# Ulimate.net
KiCad netlist of a schematic drawn in EAGLE
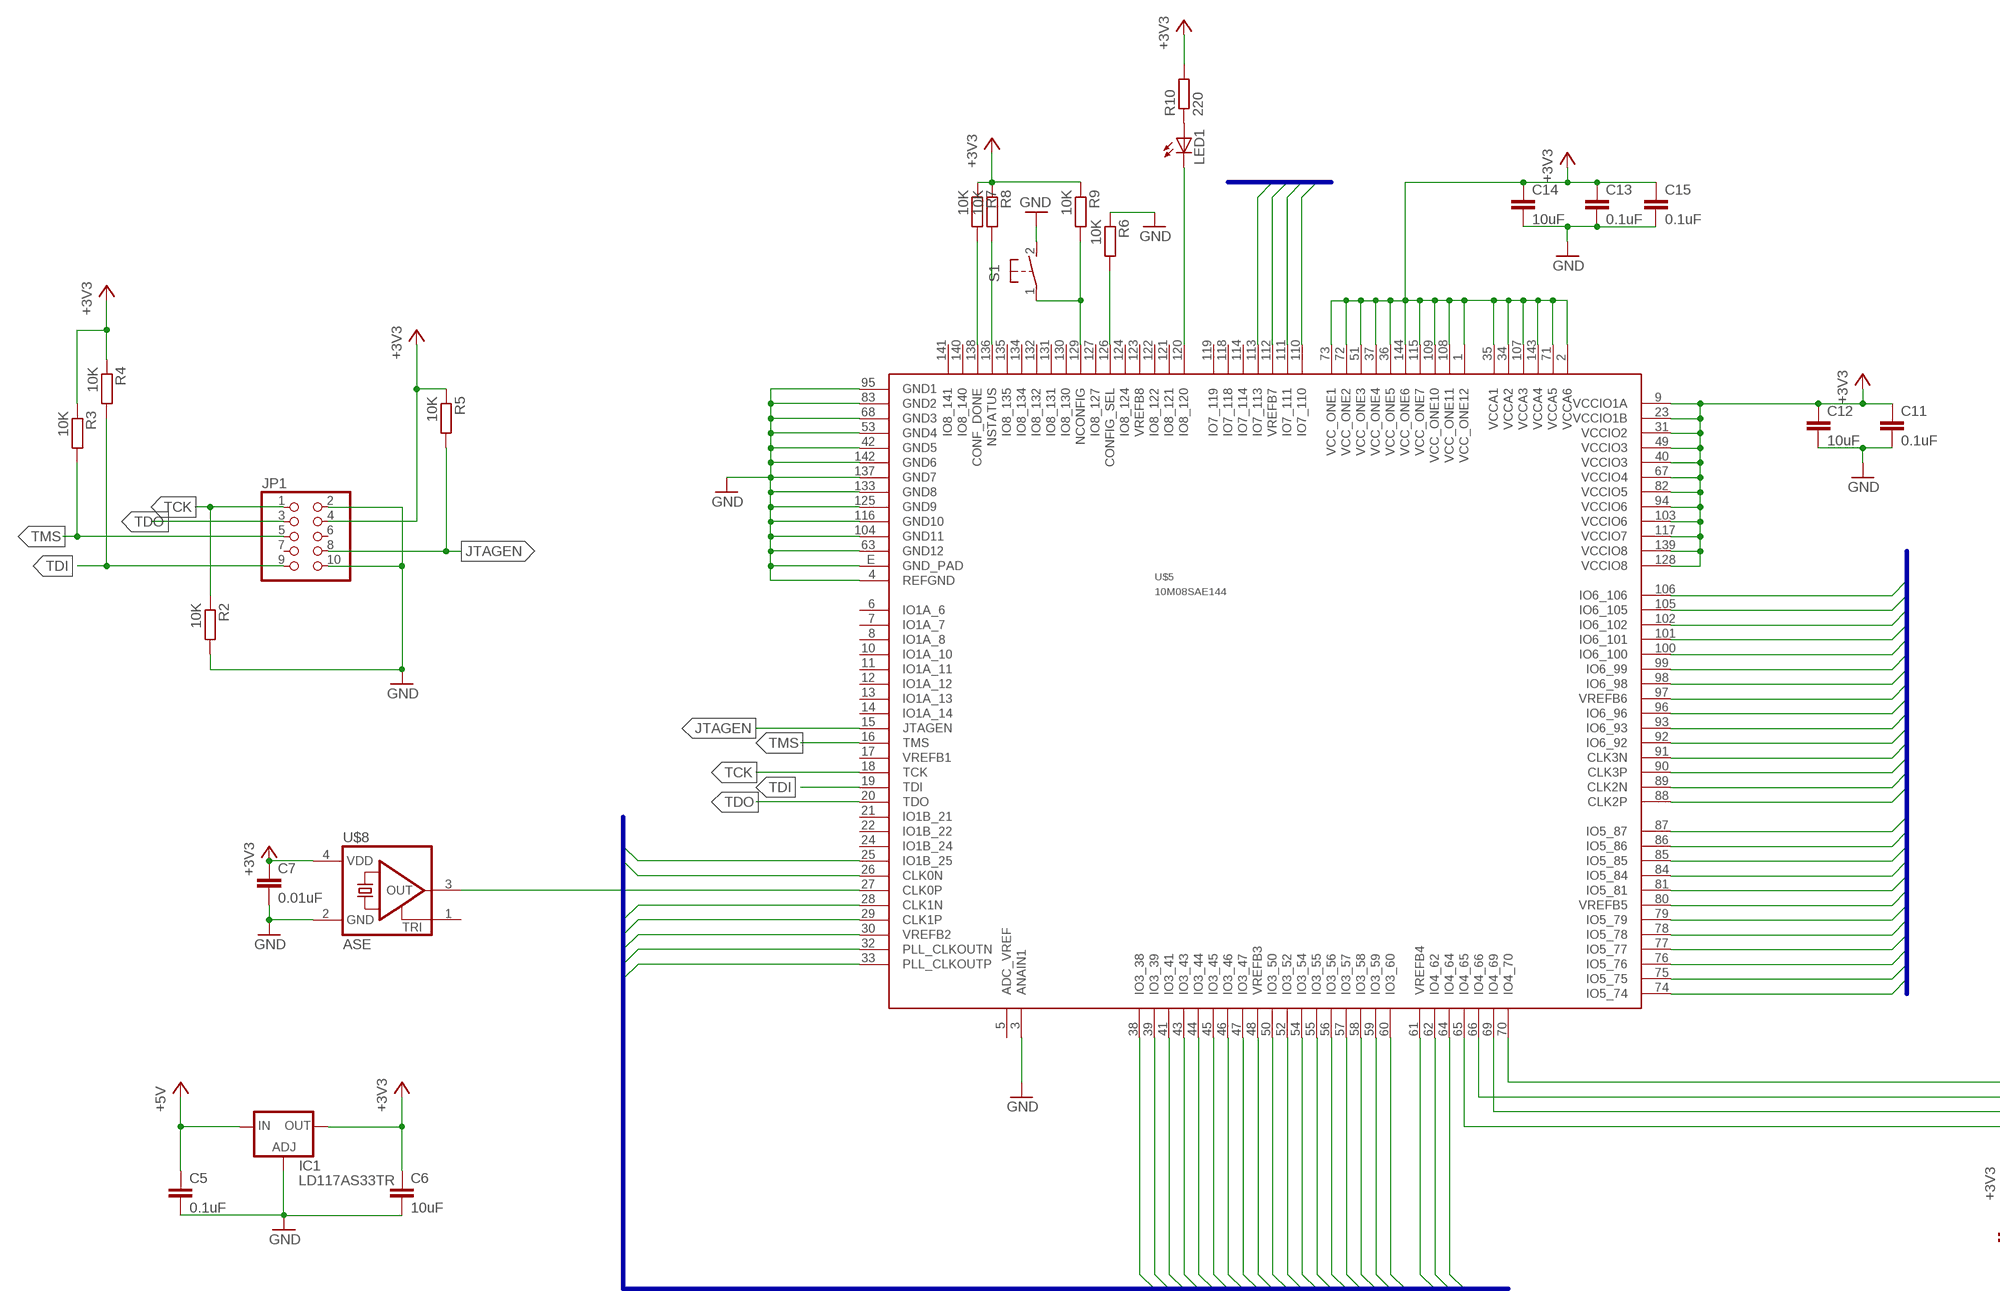
[diagram p0: schematic, sheet 1, part 1 of 2]
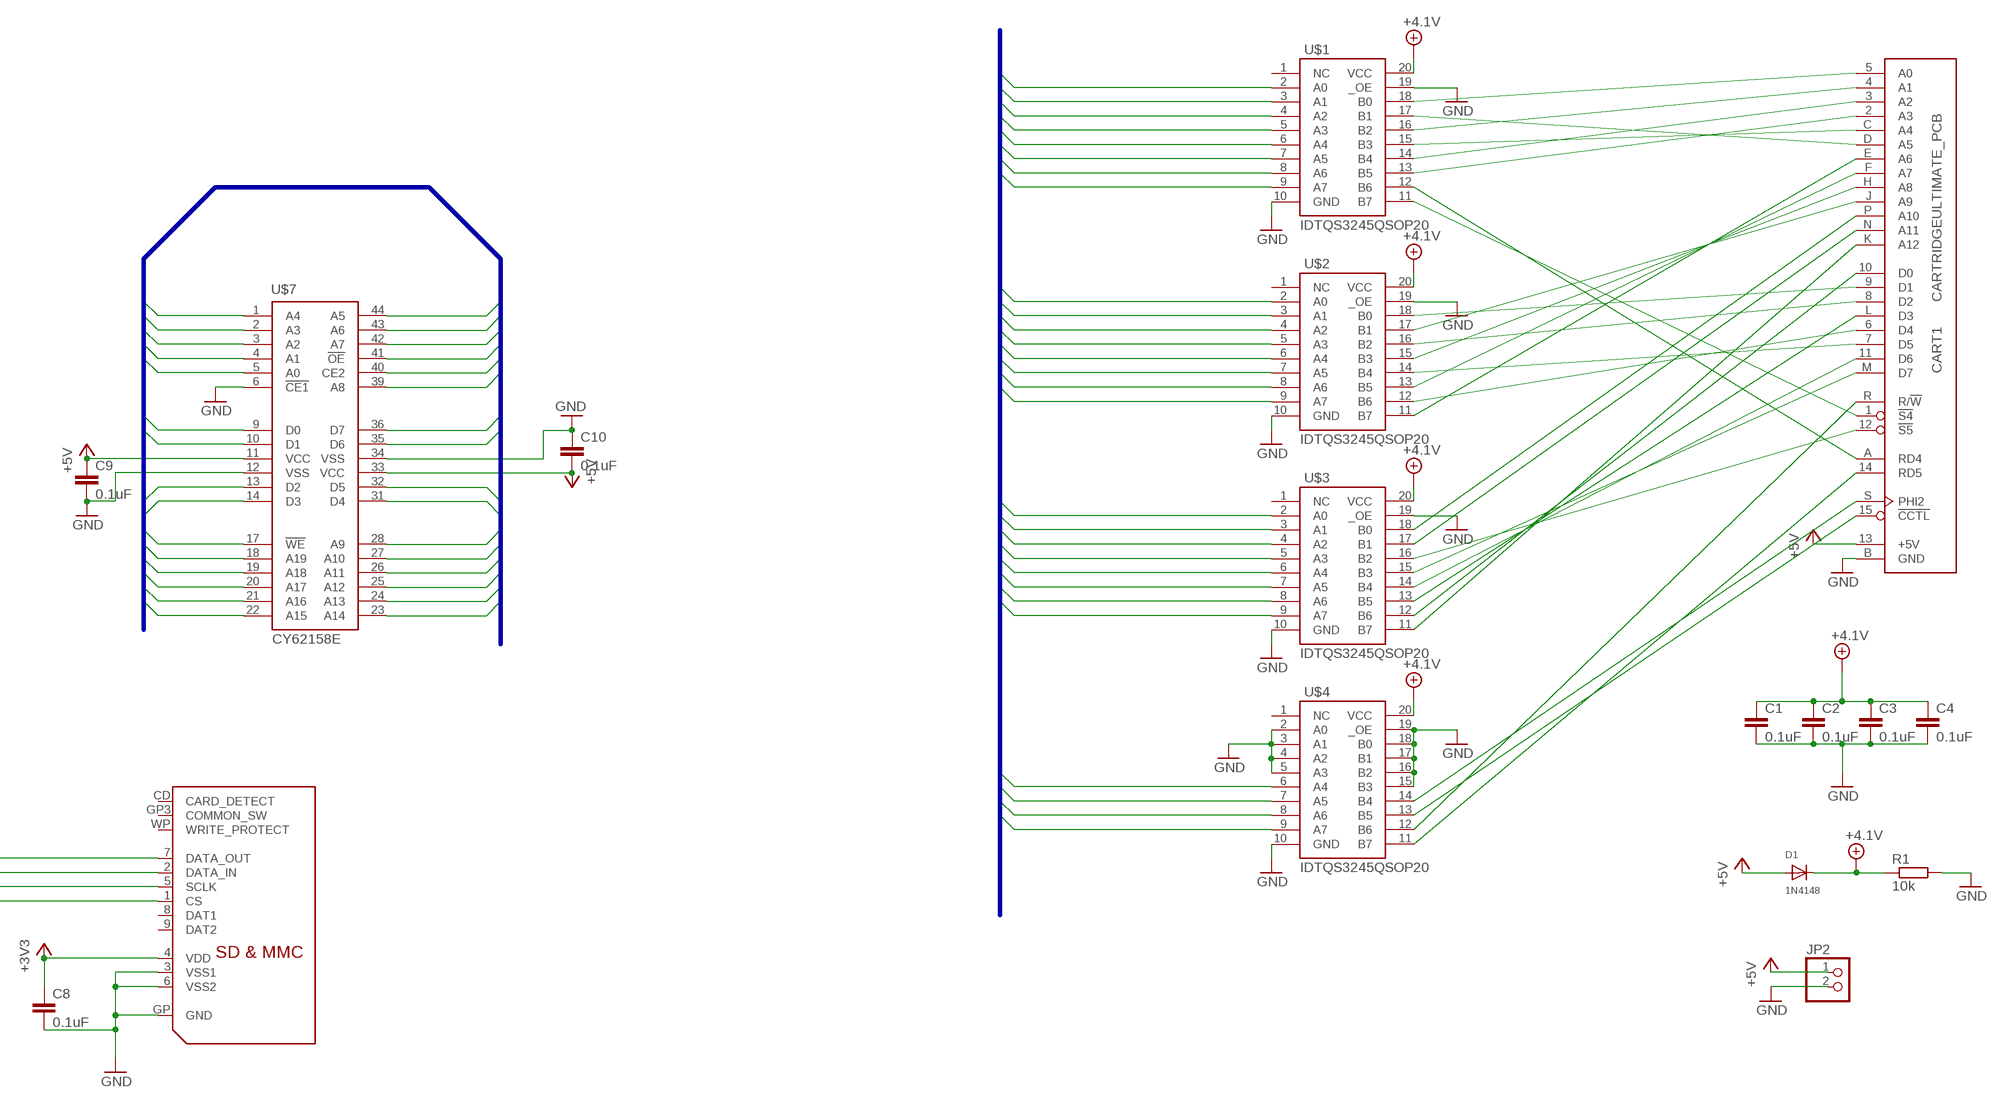
[diagram p1: schematic, sheet 1, part 2 of 2]

(export (version "E")
  (design (tool "Eeschema 10.0.6"))
  (components
    (comp (ref "C1")
      (value "0.1uF")
      (footprint "eagle-import:C0805K")
      (libsource (lib "eagle-import") (part "C-EUC0805K"))
    )
    (comp (ref "C2")
      (value "0.1uF")
      (footprint "eagle-import:C0805K")
      (libsource (lib "eagle-import") (part "C-EUC0805K"))
    )
    (comp (ref "C3")
      (value "0.1uF")
      (footprint "eagle-import:C0805K")
      (libsource (lib "eagle-import") (part "C-EUC0805K"))
    )
    (comp (ref "C4")
      (value "0.1uF")
      (footprint "eagle-import:C0805K")
      (libsource (lib "eagle-import") (part "C-EUC0805K"))
    )
    (comp (ref "C5")
      (value "0.1uF")
      (footprint "eagle-import:C0805K")
      (libsource (lib "eagle-import") (part "C-EUC0805K"))
    )
    (comp (ref "C6")
      (value "10uF")
      (footprint "eagle-import:C0805K")
      (libsource (lib "eagle-import") (part "C-EUC0805K"))
    )
    (comp (ref "C7")
      (value "0.01uF")
      (footprint "eagle-import:C0805K")
      (libsource (lib "eagle-import") (part "C-EUC0805K"))
    )
    (comp (ref "C8")
      (value "0.1uF")
      (footprint "eagle-import:C0805K")
      (libsource (lib "eagle-import") (part "C-EUC0805K"))
    )
    (comp (ref "C9")
      (value "0.1uF")
      (footprint "eagle-import:C0805K")
      (libsource (lib "eagle-import") (part "C-EUC0805K"))
    )
    (comp (ref "C10")
      (value "0.1uF")
      (footprint "eagle-import:C0805K")
      (libsource (lib "eagle-import") (part "C-EUC0805K"))
    )
    (comp (ref "C11")
      (value "0.1uF")
      (footprint "eagle-import:C0805K")
      (libsource (lib "eagle-import") (part "C-EUC0805K"))
    )
    (comp (ref "C12")
      (value "10uF")
      (footprint "eagle-import:C0805K")
      (libsource (lib "eagle-import") (part "C-EUC0805K"))
    )
    (comp (ref "C13")
      (value "0.1uF")
      (footprint "eagle-import:C0805K")
      (libsource (lib "eagle-import") (part "C-EUC0805K"))
    )
    (comp (ref "C14")
      (value "10uF")
      (footprint "eagle-import:C0805K")
      (libsource (lib "eagle-import") (part "C-EUC0805K"))
    )
    (comp (ref "C15")
      (value "0.1uF")
      (footprint "eagle-import:C0805K")
      (libsource (lib "eagle-import") (part "C-EUC0805K"))
    )
    (comp (ref "CART1")
      (value "CARTRIDGEULTIMATE_PCB")
      (footprint "eagle-import:CART_ULTIMATE")
      (libsource (lib "eagle-import") (part "CARTRIDGEULTIMATE_PCB"))
    )
    (comp (ref "D1")
      (value "1N4148")
      (footprint "eagle-import:SOD-123FL")
      (libsource (lib "eagle-import") (part "DIODE_SOD-123FL"))
    )
    (comp (ref "IC1")
      (value "LD117AS33TR")
      (footprint "eagle-import:SOT223")
      (libsource (lib "eagle-import") (part "LD117A?S33TR"))
    )
    (comp (ref "JP1")
      (value "PINHD-2X5")
      (footprint "eagle-import:2X05")
      (libsource (lib "eagle-import") (part "PINHD-2X5"))
    )
    (comp (ref "JP2")
      (value "PINHD-1X2")
      (footprint "eagle-import:1X02")
      (libsource (lib "eagle-import") (part "PINHD-1X2"))
    )
    (comp (ref "LED1")
      (value "LEDSML0805")
      (footprint "eagle-import:SML0805")
      (libsource (lib "eagle-import") (part "LEDSML0805"))
    )
    (comp (ref "R1")
      (value "10k")
      (footprint "eagle-import:R0805")
      (libsource (lib "eagle-import") (part "R-EU_R0805"))
    )
    (comp (ref "R2")
      (value "10K")
      (footprint "eagle-import:R0805")
      (libsource (lib "eagle-import") (part "R-EU_R0805"))
    )
    (comp (ref "R3")
      (value "10K")
      (footprint "eagle-import:R0805")
      (libsource (lib "eagle-import") (part "R-EU_R0805"))
    )
    (comp (ref "R4")
      (value "10K")
      (footprint "eagle-import:R0805")
      (libsource (lib "eagle-import") (part "R-EU_R0805"))
    )
    (comp (ref "R5")
      (value "10K")
      (footprint "eagle-import:R0805")
      (libsource (lib "eagle-import") (part "R-EU_R0805"))
    )
    (comp (ref "R6")
      (value "10K")
      (footprint "eagle-import:R0805")
      (libsource (lib "eagle-import") (part "R-EU_R0805"))
    )
    (comp (ref "R7")
      (value "10K")
      (footprint "eagle-import:R0805")
      (libsource (lib "eagle-import") (part "R-EU_R0805"))
    )
    (comp (ref "R8")
      (value "10K")
      (footprint "eagle-import:R0805")
      (libsource (lib "eagle-import") (part "R-EU_R0805"))
    )
    (comp (ref "R9")
      (value "10K")
      (footprint "eagle-import:R0805")
      (libsource (lib "eagle-import") (part "R-EU_R0805"))
    )
    (comp (ref "R10")
      (value "220")
      (footprint "eagle-import:R0805")
      (libsource (lib "eagle-import") (part "R-EU_R0805"))
    )
    (comp (ref "S1")
      (value "31-XXSKINNY")
      (footprint "eagle-import:B3F-31XX-SKINNIER")
      (libsource (lib "eagle-import") (part "31-XXSKINNY"))
    )
    (comp (ref "U$1")
      (value "IDTQS3245QSOP20")
      (footprint "eagle-import:QSOP20")
      (libsource (lib "eagle-import") (part "IDTQS3245QSOP20"))
    )
    (comp (ref "U$2")
      (value "IDTQS3245QSOP20")
      (footprint "eagle-import:QSOP20")
      (libsource (lib "eagle-import") (part "IDTQS3245QSOP20"))
    )
    (comp (ref "U$3")
      (value "IDTQS3245QSOP20")
      (footprint "eagle-import:QSOP20")
      (libsource (lib "eagle-import") (part "IDTQS3245QSOP20"))
    )
    (comp (ref "U$4")
      (value "IDTQS3245QSOP20")
      (footprint "eagle-import:QSOP20")
      (libsource (lib "eagle-import") (part "IDTQS3245QSOP20"))
    )
    (comp (ref "U$5")
      (value "10M08SAE144")
      (footprint "eagle-import:EQFP144")
      (libsource (lib "eagle-import") (part "10M08SAE144"))
    )
    (comp (ref "U$6")
      (value "SDMMC06132")
      (footprint "eagle-import:06132")
      (libsource (lib "eagle-import") (part "SDMMC06132"))
    )
    (comp (ref "U$7")
      (value "CY62158E")
      (footprint "eagle-import:TSOP44-II")
      (libsource (lib "eagle-import") (part "CY62158E"))
    )
    (comp (ref "U$8")
      (value "ASE")
      (footprint "eagle-import:ASE")
      (libsource (lib "eagle-import") (part "ASE"))
    )
  )
  (nets
    (net (code "1") (name "+3V3") (class "Default")
      (node (ref "C11") (pin "1") (pinfunction "1_1") (pintype "passive"))
      (node (ref "C12") (pin "1") (pinfunction "1_1") (pintype "passive"))
      (node (ref "C13") (pin "1") (pinfunction "1_1") (pintype "passive"))
      (node (ref "C14") (pin "1") (pinfunction "1_1") (pintype "passive"))
      (node (ref "C15") (pin "1") (pinfunction "1_1") (pintype "passive"))
      (node (ref "C6") (pin "1") (pinfunction "1_1") (pintype "passive"))
      (node (ref "C7") (pin "1") (pinfunction "1_1") (pintype "passive"))
      (node (ref "C8") (pin "1") (pinfunction "1_1") (pintype "passive"))
      (node (ref "IC1") (pin "4") (pinfunction "OUT_4") (pintype "passive"))
      (node (ref "JP1") (pin "4") (pinfunction "4_4") (pintype "passive"))
      (node (ref "R10") (pin "2") (pinfunction "2_2") (pintype "passive"))
      (node (ref "R3") (pin "1") (pinfunction "1_1") (pintype "passive"))
      (node (ref "R4") (pin "1") (pinfunction "1_1") (pintype "passive"))
      (node (ref "R5") (pin "1") (pinfunction "1_1") (pintype "passive"))
      (node (ref "R7") (pin "1") (pinfunction "1_1") (pintype "passive"))
      (node (ref "R8") (pin "1") (pinfunction "1_1") (pintype "passive"))
      (node (ref "R9") (pin "1") (pinfunction "1_1") (pintype "passive"))
      (node (ref "U$5") (pin "1") (pinfunction "VCC_ONE12_1") (pintype "bidirectional"))
      (node (ref "U$5") (pin "103") (pinfunction "VCCIO6_103") (pintype "bidirectional"))
      (node (ref "U$5") (pin "107") (pinfunction "VCCA3_107") (pintype "bidirectional"))
      (node (ref "U$5") (pin "108") (pinfunction "VCC_ONE11_108") (pintype "bidirectional"))
      (node (ref "U$5") (pin "109") (pinfunction "VCC_ONE10_109") (pintype "bidirectional"))
      (node (ref "U$5") (pin "115") (pinfunction "VCC_ONE7_115") (pintype "bidirectional"))
      (node (ref "U$5") (pin "117") (pinfunction "VCCIO7_117") (pintype "bidirectional"))
      (node (ref "U$5") (pin "128") (pinfunction "VCCIO8_128") (pintype "bidirectional"))
      (node (ref "U$5") (pin "139") (pinfunction "VCCIO8_139") (pintype "bidirectional"))
      (node (ref "U$5") (pin "143") (pinfunction "VCCA4_143") (pintype "bidirectional"))
      (node (ref "U$5") (pin "144") (pinfunction "VCC_ONE6_144") (pintype "bidirectional"))
      (node (ref "U$5") (pin "2") (pinfunction "VCCA6_2") (pintype "bidirectional"))
      (node (ref "U$5") (pin "23") (pinfunction "VCCIO1B_23") (pintype "bidirectional"))
      (node (ref "U$5") (pin "31") (pinfunction "VCCIO2_31") (pintype "bidirectional"))
      (node (ref "U$5") (pin "34") (pinfunction "VCCA2_34") (pintype "bidirectional"))
      (node (ref "U$5") (pin "35") (pinfunction "VCCA1_35") (pintype "bidirectional"))
      (node (ref "U$5") (pin "36") (pinfunction "VCC_ONE5_36") (pintype "bidirectional"))
      (node (ref "U$5") (pin "37") (pinfunction "VCC_ONE4_37") (pintype "bidirectional"))
      (node (ref "U$5") (pin "40") (pinfunction "VCCIO3_40") (pintype "bidirectional"))
      (node (ref "U$5") (pin "49") (pinfunction "VCCIO3_49") (pintype "bidirectional"))
      (node (ref "U$5") (pin "51") (pinfunction "VCC_ONE3_51") (pintype "bidirectional"))
      (node (ref "U$5") (pin "67") (pinfunction "VCCIO4_67") (pintype "bidirectional"))
      (node (ref "U$5") (pin "71") (pinfunction "VCCA5_71") (pintype "bidirectional"))
      (node (ref "U$5") (pin "72") (pinfunction "VCC_ONE2_72") (pintype "bidirectional"))
      (node (ref "U$5") (pin "73") (pinfunction "VCC_ONE1_73") (pintype "bidirectional"))
      (node (ref "U$5") (pin "82") (pinfunction "VCCIO5_82") (pintype "bidirectional"))
      (node (ref "U$5") (pin "9") (pinfunction "VCCIO1A_9") (pintype "bidirectional"))
      (node (ref "U$5") (pin "94") (pinfunction "VCCIO6_94") (pintype "bidirectional"))
      (node (ref "U$6") (pin "4") (pinfunction "VDD_4") (pintype "power_in"))
      (node (ref "U$8") (pin "4") (pinfunction "VDD_4") (pintype "power_in"))
    )
    (net (code "2") (name "+4.1V") (class "Default")
      (node (ref "C1") (pin "1") (pinfunction "1_1") (pintype "passive"))
      (node (ref "C2") (pin "1") (pinfunction "1_1") (pintype "passive"))
      (node (ref "C3") (pin "1") (pinfunction "1_1") (pintype "passive"))
      (node (ref "C4") (pin "1") (pinfunction "1_1") (pintype "passive"))
      (node (ref "D1") (pin "C") (pinfunction "C_C") (pintype "passive"))
      (node (ref "R1") (pin "1") (pinfunction "1_1") (pintype "passive"))
      (node (ref "U$1") (pin "20") (pinfunction "VCC_20") (pintype "power_in"))
      (node (ref "U$2") (pin "20") (pinfunction "VCC_20") (pintype "power_in"))
      (node (ref "U$3") (pin "20") (pinfunction "VCC_20") (pintype "power_in"))
      (node (ref "U$4") (pin "20") (pinfunction "VCC_20") (pintype "power_in"))
    )
    (net (code "3") (name "+5V") (class "Default")
      (node (ref "C10") (pin "2") (pinfunction "2_2") (pintype "passive"))
      (node (ref "C5") (pin "1") (pinfunction "1_1") (pintype "passive"))
      (node (ref "C9") (pin "1") (pinfunction "1_1") (pintype "passive"))
      (node (ref "CART1") (pin "13") (pinfunction "+5V_13") (pintype "power_in"))
      (node (ref "D1") (pin "A") (pinfunction "A_A") (pintype "passive"))
      (node (ref "IC1") (pin "3") (pinfunction "IN_3") (pintype "input"))
      (node (ref "JP2") (pin "1") (pinfunction "1_1") (pintype "passive"))
      (node (ref "U$7") (pin "11") (pinfunction "VCC_11") (pintype "bidirectional"))
      (node (ref "U$7") (pin "33") (pinfunction "VCC_33") (pintype "bidirectional"))
    )
    (net (code "4") (name "/A0") (class "Default")
      (node (ref "U$5") (pin "96") (pinfunction "IO6_96_96") (pintype "bidirectional"))
      (node (ref "U$7") (pin "5") (pinfunction "A0_5") (pintype "bidirectional"))
    )
    (net (code "5") (name "/A1") (class "Default")
      (node (ref "U$5") (pin "97") (pinfunction "VREFB6_97") (pintype "bidirectional"))
      (node (ref "U$7") (pin "4") (pinfunction "A1_4") (pintype "bidirectional"))
    )
    (net (code "6") (name "/A2") (class "Default")
      (node (ref "U$5") (pin "98") (pinfunction "IO6_98_98") (pintype "bidirectional"))
      (node (ref "U$7") (pin "3") (pinfunction "A2_3") (pintype "bidirectional"))
    )
    (net (code "7") (name "/A3") (class "Default")
      (node (ref "U$5") (pin "99") (pinfunction "IO6_99_99") (pintype "bidirectional"))
      (node (ref "U$7") (pin "2") (pinfunction "A3_2") (pintype "bidirectional"))
    )
    (net (code "8") (name "/A4") (class "Default")
      (node (ref "U$5") (pin "100") (pinfunction "IO6_100_100") (pintype "bidirectional"))
      (node (ref "U$7") (pin "1") (pinfunction "A4_1") (pintype "bidirectional"))
    )
    (net (code "9") (name "/A5") (class "Default")
      (node (ref "U$5") (pin "105") (pinfunction "IO6_105_105") (pintype "bidirectional"))
      (node (ref "U$7") (pin "44") (pinfunction "A5_44") (pintype "bidirectional"))
    )
    (net (code "10") (name "/A6") (class "Default")
      (node (ref "U$5") (pin "102") (pinfunction "IO6_102_102") (pintype "bidirectional"))
      (node (ref "U$7") (pin "43") (pinfunction "A6_43") (pintype "bidirectional"))
    )
    (net (code "11") (name "/A7") (class "Default")
      (node (ref "U$5") (pin "101") (pinfunction "IO6_101_101") (pintype "bidirectional"))
      (node (ref "U$7") (pin "42") (pinfunction "A7_42") (pintype "bidirectional"))
    )
    (net (code "12") (name "/A8") (class "Default")
      (node (ref "U$5") (pin "111") (pinfunction "IO7_111_111") (pintype "bidirectional"))
      (node (ref "U$7") (pin "39") (pinfunction "A8_39") (pintype "bidirectional"))
    )
    (net (code "13") (name "/A9") (class "Default")
      (node (ref "U$5") (pin "76") (pinfunction "IO5_76_76") (pintype "bidirectional"))
      (node (ref "U$7") (pin "28") (pinfunction "A9_28") (pintype "bidirectional"))
    )
    (net (code "14") (name "/A10") (class "Default")
      (node (ref "U$5") (pin "77") (pinfunction "IO5_77_77") (pintype "bidirectional"))
      (node (ref "U$7") (pin "27") (pinfunction "A10_27") (pintype "bidirectional"))
    )
    (net (code "15") (name "/A11") (class "Default")
      (node (ref "U$5") (pin "78") (pinfunction "IO5_78_78") (pintype "bidirectional"))
      (node (ref "U$7") (pin "26") (pinfunction "A11_26") (pintype "bidirectional"))
    )
    (net (code "16") (name "/A12") (class "Default")
      (node (ref "U$5") (pin "79") (pinfunction "IO5_79_79") (pintype "bidirectional"))
      (node (ref "U$7") (pin "25") (pinfunction "A12_25") (pintype "bidirectional"))
    )
    (net (code "17") (name "/A13") (class "Default")
      (node (ref "U$5") (pin "80") (pinfunction "VREFB5_80") (pintype "bidirectional"))
      (node (ref "U$7") (pin "24") (pinfunction "A13_24") (pintype "bidirectional"))
    )
    (net (code "18") (name "/A14") (class "Default")
      (node (ref "U$5") (pin "81") (pinfunction "IO5_81_81") (pintype "bidirectional"))
      (node (ref "U$7") (pin "23") (pinfunction "A14_23") (pintype "bidirectional"))
    )
    (net (code "19") (name "/A15") (class "Default")
      (node (ref "U$5") (pin "84") (pinfunction "IO5_84_84") (pintype "bidirectional"))
      (node (ref "U$7") (pin "22") (pinfunction "A15_22") (pintype "bidirectional"))
    )
    (net (code "20") (name "/A16") (class "Default")
      (node (ref "U$5") (pin "85") (pinfunction "IO5_85_85") (pintype "bidirectional"))
      (node (ref "U$7") (pin "21") (pinfunction "A16_21") (pintype "bidirectional"))
    )
    (net (code "21") (name "/A17") (class "Default")
      (node (ref "U$5") (pin "86") (pinfunction "IO5_86_86") (pintype "bidirectional"))
      (node (ref "U$7") (pin "20") (pinfunction "A17_20") (pintype "bidirectional"))
    )
    (net (code "22") (name "/A18") (class "Default")
      (node (ref "U$5") (pin "87") (pinfunction "IO5_87_87") (pintype "bidirectional"))
      (node (ref "U$7") (pin "19") (pinfunction "A18_19") (pintype "bidirectional"))
    )
    (net (code "23") (name "/A19") (class "Default")
      (node (ref "U$5") (pin "88") (pinfunction "CLK2P_88") (pintype "bidirectional"))
      (node (ref "U$7") (pin "18") (pinfunction "A19_18") (pintype "bidirectional"))
    )
    (net (code "24") (name "/CART_A0") (class "Default")
      (node (ref "U$1") (pin "2") (pinfunction "A0_2") (pintype "bidirectional"))
      (node (ref "U$5") (pin "39") (pinfunction "IO3_39_39") (pintype "bidirectional"))
    )
    (net (code "25") (name "/CART_A1") (class "Default")
      (node (ref "U$1") (pin "4") (pinfunction "A2_4") (pintype "bidirectional"))
      (node (ref "U$5") (pin "33") (pinfunction "PLL_CLKOUTP_33") (pintype "bidirectional"))
    )
    (net (code "26") (name "/CART_A2") (class "Default")
      (node (ref "U$1") (pin "6") (pinfunction "A4_6") (pintype "bidirectional"))
      (node (ref "U$5") (pin "30") (pinfunction "VREFB2_30") (pintype "bidirectional"))
    )
    (net (code "27") (name "/CART_A3") (class "Default")
      (node (ref "U$1") (pin "7") (pinfunction "A5_7") (pintype "bidirectional"))
      (node (ref "U$5") (pin "29") (pinfunction "CLK1P_29") (pintype "bidirectional"))
    )
    (net (code "28") (name "/CART_A4") (class "Default")
      (node (ref "U$1") (pin "5") (pinfunction "A3_5") (pintype "bidirectional"))
      (node (ref "U$5") (pin "32") (pinfunction "PLL_CLKOUTN_32") (pintype "bidirectional"))
    )
    (net (code "29") (name "/CART_A5") (class "Default")
      (node (ref "U$1") (pin "3") (pinfunction "A1_3") (pintype "bidirectional"))
      (node (ref "U$5") (pin "38") (pinfunction "IO3_38_38") (pintype "bidirectional"))
    )
    (net (code "30") (name "/CART_A6") (class "Default")
      (node (ref "U$2") (pin "9") (pinfunction "A7_9") (pintype "bidirectional"))
      (node (ref "U$5") (pin "41") (pinfunction "IO3_41_41") (pintype "bidirectional"))
    )
    (net (code "31") (name "/CART_A7") (class "Default")
      (node (ref "U$2") (pin "7") (pinfunction "A5_7") (pintype "bidirectional"))
      (node (ref "U$5") (pin "44") (pinfunction "IO3_44_44") (pintype "bidirectional"))
    )
    (net (code "32") (name "/CART_A8") (class "Default")
      (node (ref "U$2") (pin "5") (pinfunction "A3_5") (pintype "bidirectional"))
      (node (ref "U$5") (pin "46") (pinfunction "IO3_46_46") (pintype "bidirectional"))
    )
    (net (code "33") (name "/CART_A9") (class "Default")
      (node (ref "U$2") (pin "3") (pinfunction "A1_3") (pintype "bidirectional"))
      (node (ref "U$5") (pin "48") (pinfunction "VREFB3_48") (pintype "bidirectional"))
    )
    (net (code "34") (name "/CART_A10") (class "Default")
      (node (ref "U$3") (pin "2") (pinfunction "A0_2") (pintype "bidirectional"))
      (node (ref "U$5") (pin "60") (pinfunction "IO3_60_60") (pintype "bidirectional"))
    )
    (net (code "35") (name "/CART_A11") (class "Default")
      (node (ref "U$3") (pin "3") (pinfunction "A1_3") (pintype "bidirectional"))
      (node (ref "U$5") (pin "59") (pinfunction "IO3_59_59") (pintype "bidirectional"))
    )
    (net (code "36") (name "/CART_A12") (class "Default")
      (node (ref "U$3") (pin "9") (pinfunction "A7_9") (pintype "bidirectional"))
      (node (ref "U$5") (pin "52") (pinfunction "IO3_52_52") (pintype "bidirectional"))
    )
    (net (code "37") (name "/CART_CTL") (class "Default")
      (node (ref "U$4") (pin "7") (pinfunction "A5_7") (pintype "bidirectional"))
      (node (ref "U$5") (pin "64") (pinfunction "IO4_64_64") (pintype "bidirectional"))
    )
    (net (code "38") (name "/CART_D0") (class "Default")
      (node (ref "U$3") (pin "8") (pinfunction "A6_8") (pintype "bidirectional"))
      (node (ref "U$5") (pin "54") (pinfunction "IO3_54_54") (pintype "bidirectional"))
    )
    (net (code "39") (name "/CART_D1") (class "Default")
      (node (ref "U$2") (pin "2") (pinfunction "A0_2") (pintype "bidirectional"))
      (node (ref "U$5") (pin "50") (pinfunction "IO3_50_50") (pintype "bidirectional"))
    )
    (net (code "40") (name "/CART_D2") (class "Default")
      (node (ref "U$2") (pin "4") (pinfunction "A2_4") (pintype "bidirectional"))
      (node (ref "U$5") (pin "47") (pinfunction "IO3_47_47") (pintype "bidirectional"))
    )
    (net (code "41") (name "/CART_D3") (class "Default")
      (node (ref "U$3") (pin "7") (pinfunction "A5_7") (pintype "bidirectional"))
      (node (ref "U$5") (pin "55") (pinfunction "IO3_55_55") (pintype "bidirectional"))
    )
    (net (code "42") (name "/CART_D4") (class "Default")
      (node (ref "U$2") (pin "8") (pinfunction "A6_8") (pintype "bidirectional"))
      (node (ref "U$5") (pin "43") (pinfunction "IO3_43_43") (pintype "bidirectional"))
    )
    (net (code "43") (name "/CART_D5") (class "Default")
      (node (ref "U$2") (pin "6") (pinfunction "A4_6") (pintype "bidirectional"))
      (node (ref "U$5") (pin "45") (pinfunction "IO3_45_45") (pintype "bidirectional"))
    )
    (net (code "44") (name "/CART_D6") (class "Default")
      (node (ref "U$3") (pin "6") (pinfunction "A4_6") (pintype "bidirectional"))
      (node (ref "U$5") (pin "56") (pinfunction "IO3_56_56") (pintype "bidirectional"))
    )
    (net (code "45") (name "/CART_D7") (class "Default")
      (node (ref "U$3") (pin "5") (pinfunction "A3_5") (pintype "bidirectional"))
      (node (ref "U$5") (pin "57") (pinfunction "IO3_57_57") (pintype "bidirectional"))
    )
    (net (code "46") (name "/CART_PHI") (class "Default")
      (node (ref "U$4") (pin "6") (pinfunction "A4_6") (pintype "bidirectional"))
      (node (ref "U$5") (pin "26") (pinfunction "CLK0N_26") (pintype "bidirectional"))
    )
    (net (code "47") (name "/CART_RD4") (class "Default")
      (node (ref "U$1") (pin "8") (pinfunction "A6_8") (pintype "bidirectional"))
      (node (ref "U$5") (pin "25") (pinfunction "IO1B_25_25") (pintype "bidirectional"))
    )
    (net (code "48") (name "/CART_RD5") (class "Default")
      (node (ref "U$4") (pin "9") (pinfunction "A7_9") (pintype "bidirectional"))
      (node (ref "U$5") (pin "61") (pinfunction "VREFB4_61") (pintype "bidirectional"))
    )
    (net (code "49") (name "/CART_RW") (class "Default")
      (node (ref "U$4") (pin "8") (pinfunction "A6_8") (pintype "bidirectional"))
      (node (ref "U$5") (pin "62") (pinfunction "IO4_62_62") (pintype "bidirectional"))
    )
    (net (code "50") (name "/CART_S4") (class "Default")
      (node (ref "U$1") (pin "9") (pinfunction "A7_9") (pintype "bidirectional"))
      (node (ref "U$5") (pin "28") (pinfunction "CLK1N_28") (pintype "bidirectional"))
    )
    (net (code "51") (name "/CART_S5") (class "Default")
      (node (ref "U$3") (pin "4") (pinfunction "A2_4") (pintype "bidirectional"))
      (node (ref "U$5") (pin "58") (pinfunction "IO3_58_58") (pintype "bidirectional"))
    )
    (net (code "52") (name "/CE") (class "Default")
      (node (ref "U$5") (pin "110") (pinfunction "IO7_110_110") (pintype "bidirectional"))
      (node (ref "U$7") (pin "40") (pinfunction "CE2_40") (pintype "bidirectional"))
    )
    (net (code "53") (name "/D0") (class "Default")
      (node (ref "U$5") (pin "93") (pinfunction "IO6_93_93") (pintype "bidirectional"))
      (node (ref "U$7") (pin "9") (pinfunction "D0_9") (pintype "bidirectional"))
    )
    (net (code "54") (name "/D1") (class "Default")
      (node (ref "U$5") (pin "92") (pinfunction "IO6_92_92") (pintype "bidirectional"))
      (node (ref "U$7") (pin "10") (pinfunction "D1_10") (pintype "bidirectional"))
    )
    (net (code "55") (name "/D2") (class "Default")
      (node (ref "U$5") (pin "91") (pinfunction "CLK3N_91") (pintype "bidirectional"))
      (node (ref "U$7") (pin "13") (pinfunction "D2_13") (pintype "bidirectional"))
    )
    (net (code "56") (name "/D3") (class "Default")
      (node (ref "U$5") (pin "90") (pinfunction "CLK3P_90") (pintype "bidirectional"))
      (node (ref "U$7") (pin "14") (pinfunction "D3_14") (pintype "bidirectional"))
    )
    (net (code "57") (name "/D4") (class "Default")
      (node (ref "U$5") (pin "75") (pinfunction "IO5_75_75") (pintype "bidirectional"))
      (node (ref "U$7") (pin "31") (pinfunction "D4_31") (pintype "bidirectional"))
    )
    (net (code "58") (name "/D5") (class "Default")
      (node (ref "U$5") (pin "74") (pinfunction "IO5_74_74") (pintype "bidirectional"))
      (node (ref "U$7") (pin "32") (pinfunction "D5_32") (pintype "bidirectional"))
    )
    (net (code "59") (name "/D6") (class "Default")
      (node (ref "U$5") (pin "113") (pinfunction "IO7_113_113") (pintype "bidirectional"))
      (node (ref "U$7") (pin "35") (pinfunction "D6_35") (pintype "bidirectional"))
    )
    (net (code "60") (name "/D7") (class "Default")
      (node (ref "U$5") (pin "112") (pinfunction "VREFB7_112") (pintype "bidirectional"))
      (node (ref "U$7") (pin "36") (pinfunction "D7_36") (pintype "bidirectional"))
    )
    (net (code "63") (name "/~{OE}") (class "Default")
      (node (ref "U$5") (pin "106") (pinfunction "IO6_106_106") (pintype "bidirectional"))
      (node (ref "U$7") (pin "41") (pinfunction "~{OE}_41") (pintype "bidirectional"))
    )
    (net (code "64") (name "/~{WE}") (class "Default")
      (node (ref "U$5") (pin "89") (pinfunction "CLK2N_89") (pintype "bidirectional"))
      (node (ref "U$7") (pin "17") (pinfunction "~{WE}_17") (pintype "bidirectional"))
    )
    (net (code "65") (name "GND") (class "Default")
      (node (ref "C1") (pin "2") (pinfunction "2_2") (pintype "passive"))
      (node (ref "C10") (pin "1") (pinfunction "1_1") (pintype "passive"))
      (node (ref "C11") (pin "2") (pinfunction "2_2") (pintype "passive"))
      (node (ref "C12") (pin "2") (pinfunction "2_2") (pintype "passive"))
      (node (ref "C13") (pin "2") (pinfunction "2_2") (pintype "passive"))
      (node (ref "C14") (pin "2") (pinfunction "2_2") (pintype "passive"))
      (node (ref "C15") (pin "2") (pinfunction "2_2") (pintype "passive"))
      (node (ref "C2") (pin "2") (pinfunction "2_2") (pintype "passive"))
      (node (ref "C3") (pin "2") (pinfunction "2_2") (pintype "passive"))
      (node (ref "C4") (pin "2") (pinfunction "2_2") (pintype "passive"))
      (node (ref "C5") (pin "2") (pinfunction "2_2") (pintype "passive"))
      (node (ref "C6") (pin "2") (pinfunction "2_2") (pintype "passive"))
      (node (ref "C7") (pin "2") (pinfunction "2_2") (pintype "passive"))
      (node (ref "C8") (pin "2") (pinfunction "2_2") (pintype "passive"))
      (node (ref "C9") (pin "2") (pinfunction "2_2") (pintype "passive"))
      (node (ref "CART1") (pin "B") (pinfunction "GND_B") (pintype "power_in"))
      (node (ref "IC1") (pin "1") (pinfunction "ADJ_1") (pintype "input"))
      (node (ref "JP1") (pin "10") (pinfunction "10_10") (pintype "passive"))
      (node (ref "JP1") (pin "2") (pinfunction "2_2") (pintype "passive"))
      (node (ref "JP2") (pin "2") (pinfunction "2_2") (pintype "passive"))
      (node (ref "R1") (pin "2") (pinfunction "2_2") (pintype "passive"))
      (node (ref "R2") (pin "2") (pinfunction "2_2") (pintype "passive"))
      (node (ref "R6") (pin "1") (pinfunction "1_1") (pintype "passive"))
      (node (ref "S1") (pin "2") (pinfunction "S_2") (pintype "passive"))
      (node (ref "U$1") (pin "10") (pinfunction "GND_10") (pintype "power_in"))
      (node (ref "U$1") (pin "19") (pinfunction "_OE_19") (pintype "bidirectional"))
      (node (ref "U$2") (pin "10") (pinfunction "GND_10") (pintype "power_in"))
      (node (ref "U$2") (pin "19") (pinfunction "_OE_19") (pintype "bidirectional"))
      (node (ref "U$3") (pin "10") (pinfunction "GND_10") (pintype "power_in"))
      (node (ref "U$3") (pin "19") (pinfunction "_OE_19") (pintype "bidirectional"))
      (node (ref "U$4") (pin "10") (pinfunction "GND_10") (pintype "power_in"))
      (node (ref "U$4") (pin "15") (pinfunction "B3_15") (pintype "bidirectional"))
      (node (ref "U$4") (pin "16") (pinfunction "B2_16") (pintype "bidirectional"))
      (node (ref "U$4") (pin "17") (pinfunction "B1_17") (pintype "bidirectional"))
      (node (ref "U$4") (pin "18") (pinfunction "B0_18") (pintype "bidirectional"))
      (node (ref "U$4") (pin "19") (pinfunction "_OE_19") (pintype "bidirectional"))
      (node (ref "U$4") (pin "2") (pinfunction "A0_2") (pintype "bidirectional"))
      (node (ref "U$4") (pin "3") (pinfunction "A1_3") (pintype "bidirectional"))
      (node (ref "U$4") (pin "4") (pinfunction "A2_4") (pintype "bidirectional"))
      (node (ref "U$4") (pin "5") (pinfunction "A3_5") (pintype "bidirectional"))
      (node (ref "U$5") (pin "104") (pinfunction "GND11_104") (pintype "bidirectional"))
      (node (ref "U$5") (pin "116") (pinfunction "GND10_116") (pintype "bidirectional"))
      (node (ref "U$5") (pin "125") (pinfunction "GND9_125") (pintype "bidirectional"))
      (node (ref "U$5") (pin "133") (pinfunction "GND8_133") (pintype "bidirectional"))
      (node (ref "U$5") (pin "137") (pinfunction "GND7_137") (pintype "bidirectional"))
      (node (ref "U$5") (pin "142") (pinfunction "GND6_142") (pintype "bidirectional"))
      (node (ref "U$5") (pin "3") (pinfunction "ANAIN1_3") (pintype "bidirectional"))
      (node (ref "U$5") (pin "4") (pinfunction "REFGND_4") (pintype "bidirectional"))
      (node (ref "U$5") (pin "42") (pinfunction "GND5_42") (pintype "bidirectional"))
      (node (ref "U$5") (pin "53") (pinfunction "GND4_53") (pintype "bidirectional"))
      (node (ref "U$5") (pin "63") (pinfunction "GND12_63") (pintype "bidirectional"))
      (node (ref "U$5") (pin "68") (pinfunction "GND3_68") (pintype "bidirectional"))
      (node (ref "U$5") (pin "83") (pinfunction "GND2_83") (pintype "bidirectional"))
      (node (ref "U$5") (pin "95") (pinfunction "GND1_95") (pintype "bidirectional"))
      (node (ref "U$5") (pin "E") (pinfunction "GND_PAD_E") (pintype "bidirectional"))
      (node (ref "U$6") (pin "3") (pinfunction "VSS1_3") (pintype "power_in"))
      (node (ref "U$6") (pin "6") (pinfunction "VSS2_6") (pintype "power_in"))
      (node (ref "U$6") (pin "GP") (pinfunction "GND_GP") (pintype "power_in"))
      (node (ref "U$7") (pin "12") (pinfunction "VSS_12") (pintype "bidirectional"))
      (node (ref "U$7") (pin "34") (pinfunction "VSS_34") (pintype "bidirectional"))
      (node (ref "U$7") (pin "6") (pinfunction "~{CE1}_6") (pintype "bidirectional"))
      (node (ref "U$8") (pin "2") (pinfunction "GND_2") (pintype "power_in"))
    )
    (net (code "66") (name "JTAGEN") (class "Default")
      (node (ref "JP1") (pin "8") (pinfunction "8_8") (pintype "passive"))
      (node (ref "R5") (pin "2") (pinfunction "2_2") (pintype "passive"))
      (node (ref "U$5") (pin "15") (pinfunction "JTAGEN_15") (pintype "bidirectional"))
    )
    (net (code "67") (name "Net-(CART1-A0)") (class "Default")
      (node (ref "CART1") (pin "5") (pinfunction "A0_5") (pintype "output"))
      (node (ref "U$1") (pin "18") (pinfunction "B0_18") (pintype "bidirectional"))
    )
    (net (code "68") (name "Net-(CART1-A1)") (class "Default")
      (node (ref "CART1") (pin "4") (pinfunction "A1_4") (pintype "output"))
      (node (ref "U$1") (pin "16") (pinfunction "B2_16") (pintype "bidirectional"))
    )
    (net (code "69") (name "Net-(CART1-A2)") (class "Default")
      (node (ref "CART1") (pin "3") (pinfunction "A2_3") (pintype "output"))
      (node (ref "U$1") (pin "14") (pinfunction "B4_14") (pintype "bidirectional"))
    )
    (net (code "70") (name "Net-(CART1-A3)") (class "Default")
      (node (ref "CART1") (pin "2") (pinfunction "A3_2") (pintype "output"))
      (node (ref "U$1") (pin "13") (pinfunction "B5_13") (pintype "bidirectional"))
    )
    (net (code "71") (name "Net-(CART1-A4)") (class "Default")
      (node (ref "CART1") (pin "C") (pinfunction "A4_C") (pintype "output"))
      (node (ref "U$1") (pin "15") (pinfunction "B3_15") (pintype "bidirectional"))
    )
    (net (code "72") (name "Net-(CART1-A5)") (class "Default")
      (node (ref "CART1") (pin "D") (pinfunction "A5_D") (pintype "output"))
      (node (ref "U$1") (pin "17") (pinfunction "B1_17") (pintype "bidirectional"))
    )
    (net (code "73") (name "Net-(CART1-A6)") (class "Default")
      (node (ref "CART1") (pin "E") (pinfunction "A6_E") (pintype "output"))
      (node (ref "U$2") (pin "11") (pinfunction "B7_11") (pintype "bidirectional"))
    )
    (net (code "74") (name "Net-(CART1-A7)") (class "Default")
      (node (ref "CART1") (pin "F") (pinfunction "A7_F") (pintype "output"))
      (node (ref "U$2") (pin "13") (pinfunction "B5_13") (pintype "bidirectional"))
    )
    (net (code "75") (name "Net-(CART1-A8)") (class "Default")
      (node (ref "CART1") (pin "H") (pinfunction "A8_H") (pintype "output"))
      (node (ref "U$2") (pin "15") (pinfunction "B3_15") (pintype "bidirectional"))
    )
    (net (code "76") (name "Net-(CART1-A9)") (class "Default")
      (node (ref "CART1") (pin "J") (pinfunction "A9_J") (pintype "output"))
      (node (ref "U$2") (pin "17") (pinfunction "B1_17") (pintype "bidirectional"))
    )
    (net (code "77") (name "Net-(CART1-A10)") (class "Default")
      (node (ref "CART1") (pin "P") (pinfunction "A10_P") (pintype "output"))
      (node (ref "U$3") (pin "18") (pinfunction "B0_18") (pintype "bidirectional"))
    )
    (net (code "78") (name "Net-(CART1-A11)") (class "Default")
      (node (ref "CART1") (pin "N") (pinfunction "A11_N") (pintype "output"))
      (node (ref "U$3") (pin "17") (pinfunction "B1_17") (pintype "bidirectional"))
    )
    (net (code "79") (name "Net-(CART1-A12)") (class "Default")
      (node (ref "CART1") (pin "K") (pinfunction "A12_K") (pintype "output"))
      (node (ref "U$3") (pin "11") (pinfunction "B7_11") (pintype "bidirectional"))
    )
    (net (code "80") (name "Net-(CART1-D0)") (class "Default")
      (node (ref "CART1") (pin "10") (pinfunction "D0_10") (pintype "bidirectional"))
      (node (ref "U$3") (pin "12") (pinfunction "B6_12") (pintype "bidirectional"))
    )
    (net (code "81") (name "Net-(CART1-D1)") (class "Default")
      (node (ref "CART1") (pin "9") (pinfunction "D1_9") (pintype "bidirectional"))
      (node (ref "U$2") (pin "18") (pinfunction "B0_18") (pintype "bidirectional"))
    )
    (net (code "82") (name "Net-(CART1-D2)") (class "Default")
      (node (ref "CART1") (pin "8") (pinfunction "D2_8") (pintype "bidirectional"))
      (node (ref "U$2") (pin "16") (pinfunction "B2_16") (pintype "bidirectional"))
    )
    (net (code "83") (name "Net-(CART1-D3)") (class "Default")
      (node (ref "CART1") (pin "L") (pinfunction "D3_L") (pintype "bidirectional"))
      (node (ref "U$3") (pin "13") (pinfunction "B5_13") (pintype "bidirectional"))
    )
    (net (code "84") (name "Net-(CART1-D4)") (class "Default")
      (node (ref "CART1") (pin "6") (pinfunction "D4_6") (pintype "bidirectional"))
      (node (ref "U$2") (pin "12") (pinfunction "B6_12") (pintype "bidirectional"))
    )
    (net (code "85") (name "Net-(CART1-D5)") (class "Default")
      (node (ref "CART1") (pin "7") (pinfunction "D5_7") (pintype "bidirectional"))
      (node (ref "U$2") (pin "14") (pinfunction "B4_14") (pintype "bidirectional"))
    )
    (net (code "86") (name "Net-(CART1-D6)") (class "Default")
      (node (ref "CART1") (pin "11") (pinfunction "D6_11") (pintype "bidirectional"))
      (node (ref "U$3") (pin "14") (pinfunction "B4_14") (pintype "bidirectional"))
    )
    (net (code "87") (name "Net-(CART1-D7)") (class "Default")
      (node (ref "CART1") (pin "M") (pinfunction "D7_M") (pintype "bidirectional"))
      (node (ref "U$3") (pin "15") (pinfunction "B3_15") (pintype "bidirectional"))
    )
    (net (code "88") (name "Net-(CART1-PHI2)") (class "Default")
      (node (ref "CART1") (pin "S") (pinfunction "PHI2_S") (pintype "output"))
      (node (ref "U$4") (pin "14") (pinfunction "B4_14") (pintype "bidirectional"))
    )
    (net (code "89") (name "Net-(CART1-RD4)") (class "Default")
      (node (ref "CART1") (pin "A") (pinfunction "RD4_A") (pintype "input"))
      (node (ref "U$1") (pin "12") (pinfunction "B6_12") (pintype "bidirectional"))
    )
    (net (code "90") (name "Net-(CART1-RD5)") (class "Default")
      (node (ref "CART1") (pin "14") (pinfunction "RD5_14") (pintype "input"))
      (node (ref "U$4") (pin "11") (pinfunction "B7_11") (pintype "bidirectional"))
    )
    (net (code "91") (name "Net-(CART1-R{slash}~{W})") (class "Default")
      (node (ref "CART1") (pin "R") (pinfunction "R/~{W}_R") (pintype "output"))
      (node (ref "U$4") (pin "12") (pinfunction "B6_12") (pintype "bidirectional"))
    )
    (net (code "92") (name "Net-(CART1-~{CCTL})") (class "Default")
      (node (ref "CART1") (pin "15") (pinfunction "~{CCTL}_15") (pintype "output"))
      (node (ref "U$4") (pin "13") (pinfunction "B5_13") (pintype "bidirectional"))
    )
    (net (code "93") (name "Net-(CART1-~{S4})") (class "Default")
      (node (ref "CART1") (pin "1") (pinfunction "~{S4}_1") (pintype "output"))
      (node (ref "U$1") (pin "11") (pinfunction "B7_11") (pintype "bidirectional"))
    )
    (net (code "94") (name "Net-(CART1-~{S5})") (class "Default")
      (node (ref "CART1") (pin "12") (pinfunction "~{S5}_12") (pintype "output"))
      (node (ref "U$3") (pin "16") (pinfunction "B2_16") (pintype "bidirectional"))
    )
    (net (code "95") (name "Net-(LED1-PadA)") (class "Default")
      (node (ref "LED1") (pin "A") (pinfunction "A_A") (pintype "passive"))
      (node (ref "R10") (pin "1") (pinfunction "1_1") (pintype "passive"))
    )
    (net (code "96") (name "Net-(S1-P)") (class "Default")
      (node (ref "R9") (pin "2") (pinfunction "2_2") (pintype "passive"))
      (node (ref "S1") (pin "1") (pinfunction "P_1") (pintype "passive"))
      (node (ref "U$5") (pin "129") (pinfunction "NCONFIG_129") (pintype "bidirectional"))
    )
    (net (code "97") (name "Net-(U$5-CLK0P)") (class "Default")
      (node (ref "U$5") (pin "27") (pinfunction "CLK0P_27") (pintype "bidirectional"))
      (node (ref "U$8") (pin "3") (pinfunction "OUT_3") (pintype "output"))
    )
    (net (code "98") (name "Net-(U$5-CONFIG_SEL)") (class "Default")
      (node (ref "R6") (pin "2") (pinfunction "2_2") (pintype "passive"))
      (node (ref "U$5") (pin "126") (pinfunction "CONFIG_SEL_126") (pintype "bidirectional"))
    )
    (net (code "99") (name "Net-(U$5-CONF_DONE)") (class "Default")
      (node (ref "R7") (pin "2") (pinfunction "2_2") (pintype "passive"))
      (node (ref "U$5") (pin "138") (pinfunction "CONF_DONE_138") (pintype "bidirectional"))
    )
    (net (code "100") (name "Net-(U$5-IO4_65)") (class "Default")
      (node (ref "U$5") (pin "65") (pinfunction "IO4_65_65") (pintype "bidirectional"))
      (node (ref "U$6") (pin "1") (pinfunction "CS_1") (pintype "input"))
    )
    (net (code "101") (name "Net-(U$5-IO4_66)") (class "Default")
      (node (ref "U$5") (pin "66") (pinfunction "IO4_66_66") (pintype "bidirectional"))
      (node (ref "U$6") (pin "2") (pinfunction "DATA_IN_2") (pintype "input"))
    )
    (net (code "102") (name "Net-(U$5-IO4_69)") (class "Default")
      (node (ref "U$5") (pin "69") (pinfunction "IO4_69_69") (pintype "bidirectional"))
      (node (ref "U$6") (pin "5") (pinfunction "SCLK_5") (pintype "input"))
    )
    (net (code "103") (name "Net-(U$5-IO4_70)") (class "Default")
      (node (ref "U$5") (pin "70") (pinfunction "IO4_70_70") (pintype "bidirectional"))
      (node (ref "U$6") (pin "7") (pinfunction "DATA_OUT_7") (pintype "output"))
    )
    (net (code "104") (name "Net-(U$5-IO8_120)") (class "Default")
      (node (ref "LED1") (pin "C") (pinfunction "C_C") (pintype "passive"))
      (node (ref "U$5") (pin "120") (pinfunction "IO8_120_120") (pintype "bidirectional"))
    )
    (net (code "105") (name "Net-(U$5-NSTATUS)") (class "Default")
      (node (ref "R8") (pin "2") (pinfunction "2_2") (pintype "passive"))
      (node (ref "U$5") (pin "136") (pinfunction "NSTATUS_136") (pintype "bidirectional"))
    )
    (net (code "106") (name "TCK") (class "Default")
      (node (ref "JP1") (pin "1") (pinfunction "1_1") (pintype "passive"))
      (node (ref "R2") (pin "1") (pinfunction "1_1") (pintype "passive"))
      (node (ref "U$5") (pin "18") (pinfunction "TCK_18") (pintype "bidirectional"))
    )
    (net (code "107") (name "TDI") (class "Default")
      (node (ref "JP1") (pin "9") (pinfunction "9_9") (pintype "passive"))
      (node (ref "R4") (pin "2") (pinfunction "2_2") (pintype "passive"))
      (node (ref "U$5") (pin "19") (pinfunction "TDI_19") (pintype "bidirectional"))
    )
    (net (code "108") (name "TDO") (class "Default")
      (node (ref "JP1") (pin "3") (pinfunction "3_3") (pintype "passive"))
      (node (ref "U$5") (pin "20") (pinfunction "TDO_20") (pintype "bidirectional"))
    )
    (net (code "109") (name "TMS") (class "Default")
      (node (ref "JP1") (pin "5") (pinfunction "5_5") (pintype "passive"))
      (node (ref "R3") (pin "2") (pinfunction "2_2") (pintype "passive"))
      (node (ref "U$5") (pin "16") (pinfunction "TMS_16") (pintype "bidirectional"))
    )
    (net (code "110") (name "unconnected-(JP1-Pad6)") (class "Default")
      (node (ref "JP1") (pin "6") (pinfunction "6_6") (pintype "passive"))
    )
    (net (code "111") (name "unconnected-(JP1-Pad7)") (class "Default")
      (node (ref "JP1") (pin "7") (pinfunction "7_7") (pintype "passive"))
    )
    (net (code "112") (name "unconnected-(U$1-NC-Pad1)") (class "Default")
      (node (ref "U$1") (pin "1") (pinfunction "NC_1") (pintype "no_connect"))
    )
    (net (code "113") (name "unconnected-(U$2-NC-Pad1)") (class "Default")
      (node (ref "U$2") (pin "1") (pinfunction "NC_1") (pintype "no_connect"))
    )
    (net (code "114") (name "unconnected-(U$3-NC-Pad1)") (class "Default")
      (node (ref "U$3") (pin "1") (pinfunction "NC_1") (pintype "no_connect"))
    )
    (net (code "115") (name "unconnected-(U$4-NC-Pad1)") (class "Default")
      (node (ref "U$4") (pin "1") (pinfunction "NC_1") (pintype "no_connect"))
    )
    (net (code "116") (name "unconnected-(U$5-ADC_VREF-Pad5)") (class "Default")
      (node (ref "U$5") (pin "5") (pinfunction "ADC_VREF_5") (pintype "bidirectional"))
    )
    (net (code "117") (name "unconnected-(U$5-IO1A_6-Pad6)") (class "Default")
      (node (ref "U$5") (pin "6") (pinfunction "IO1A_6_6") (pintype "bidirectional"))
    )
    (net (code "118") (name "unconnected-(U$5-IO1A_7-Pad7)") (class "Default")
      (node (ref "U$5") (pin "7") (pinfunction "IO1A_7_7") (pintype "bidirectional"))
    )
    (net (code "119") (name "unconnected-(U$5-IO1A_8-Pad8)") (class "Default")
      (node (ref "U$5") (pin "8") (pinfunction "IO1A_8_8") (pintype "bidirectional"))
    )
    (net (code "120") (name "unconnected-(U$5-IO1A_10-Pad10)") (class "Default")
      (node (ref "U$5") (pin "10") (pinfunction "IO1A_10_10") (pintype "bidirectional"))
    )
    (net (code "121") (name "unconnected-(U$5-IO1A_11-Pad11)") (class "Default")
      (node (ref "U$5") (pin "11") (pinfunction "IO1A_11_11") (pintype "bidirectional"))
    )
    (net (code "122") (name "unconnected-(U$5-IO1A_12-Pad12)") (class "Default")
      (node (ref "U$5") (pin "12") (pinfunction "IO1A_12_12") (pintype "bidirectional"))
    )
    (net (code "123") (name "unconnected-(U$5-IO1A_13-Pad13)") (class "Default")
      (node (ref "U$5") (pin "13") (pinfunction "IO1A_13_13") (pintype "bidirectional"))
    )
    (net (code "124") (name "unconnected-(U$5-IO1A_14-Pad14)") (class "Default")
      (node (ref "U$5") (pin "14") (pinfunction "IO1A_14_14") (pintype "bidirectional"))
    )
    (net (code "125") (name "unconnected-(U$5-IO1B_21-Pad21)") (class "Default")
      (node (ref "U$5") (pin "21") (pinfunction "IO1B_21_21") (pintype "bidirectional"))
    )
    (net (code "126") (name "unconnected-(U$5-IO1B_22-Pad22)") (class "Default")
      (node (ref "U$5") (pin "22") (pinfunction "IO1B_22_22") (pintype "bidirectional"))
    )
    (net (code "127") (name "unconnected-(U$5-IO1B_24-Pad24)") (class "Default")
      (node (ref "U$5") (pin "24") (pinfunction "IO1B_24_24") (pintype "bidirectional"))
    )
    (net (code "128") (name "unconnected-(U$5-IO7_114-Pad114)") (class "Default")
      (node (ref "U$5") (pin "114") (pinfunction "IO7_114_114") (pintype "bidirectional"))
    )
    (net (code "129") (name "unconnected-(U$5-IO7_118-Pad118)") (class "Default")
      (node (ref "U$5") (pin "118") (pinfunction "IO7_118_118") (pintype "bidirectional"))
    )
    (net (code "130") (name "unconnected-(U$5-IO7_119-Pad119)") (class "Default")
      (node (ref "U$5") (pin "119") (pinfunction "IO7_119_119") (pintype "bidirectional"))
    )
    (net (code "131") (name "unconnected-(U$5-IO8_121-Pad121)") (class "Default")
      (node (ref "U$5") (pin "121") (pinfunction "IO8_121_121") (pintype "bidirectional"))
    )
    (net (code "132") (name "unconnected-(U$5-IO8_122-Pad122)") (class "Default")
      (node (ref "U$5") (pin "122") (pinfunction "IO8_122_122") (pintype "bidirectional"))
    )
    (net (code "133") (name "unconnected-(U$5-IO8_124-Pad124)") (class "Default")
      (node (ref "U$5") (pin "124") (pinfunction "IO8_124_124") (pintype "bidirectional"))
    )
    (net (code "134") (name "unconnected-(U$5-IO8_127-Pad127)") (class "Default")
      (node (ref "U$5") (pin "127") (pinfunction "IO8_127_127") (pintype "bidirectional"))
    )
    (net (code "135") (name "unconnected-(U$5-IO8_130-Pad130)") (class "Default")
      (node (ref "U$5") (pin "130") (pinfunction "IO8_130_130") (pintype "bidirectional"))
    )
    (net (code "136") (name "unconnected-(U$5-IO8_131-Pad131)") (class "Default")
      (node (ref "U$5") (pin "131") (pinfunction "IO8_131_131") (pintype "bidirectional"))
    )
    (net (code "137") (name "unconnected-(U$5-IO8_132-Pad132)") (class "Default")
      (node (ref "U$5") (pin "132") (pinfunction "IO8_132_132") (pintype "bidirectional"))
    )
    (net (code "138") (name "unconnected-(U$5-IO8_134-Pad134)") (class "Default")
      (node (ref "U$5") (pin "134") (pinfunction "IO8_134_134") (pintype "bidirectional"))
    )
    (net (code "139") (name "unconnected-(U$5-IO8_135-Pad135)") (class "Default")
      (node (ref "U$5") (pin "135") (pinfunction "IO8_135_135") (pintype "bidirectional"))
    )
    (net (code "140") (name "unconnected-(U$5-IO8_140-Pad140)") (class "Default")
      (node (ref "U$5") (pin "140") (pinfunction "IO8_140_140") (pintype "bidirectional"))
    )
    (net (code "141") (name "unconnected-(U$5-IO8_141-Pad141)") (class "Default")
      (node (ref "U$5") (pin "141") (pinfunction "IO8_141_141") (pintype "bidirectional"))
    )
    (net (code "142") (name "unconnected-(U$5-VREFB1-Pad17)") (class "Default")
      (node (ref "U$5") (pin "17") (pinfunction "VREFB1_17") (pintype "bidirectional"))
    )
    (net (code "143") (name "unconnected-(U$5-VREFB8-Pad123)") (class "Default")
      (node (ref "U$5") (pin "123") (pinfunction "VREFB8_123") (pintype "bidirectional"))
    )
    (net (code "144") (name "unconnected-(U$6-CARD_DETECT-PadCD)") (class "Default")
      (node (ref "U$6") (pin "CD") (pinfunction "CARD_DETECT_CD") (pintype "passive"))
    )
    (net (code "145") (name "unconnected-(U$6-COMMON_SW-PadGP3)") (class "Default")
      (node (ref "U$6") (pin "GP3") (pinfunction "COMMON_SW_GP3") (pintype "passive"))
    )
    (net (code "146") (name "unconnected-(U$6-DAT1-Pad8)") (class "Default")
      (node (ref "U$6") (pin "8") (pinfunction "DAT1_8") (pintype "bidirectional"))
    )
    (net (code "147") (name "unconnected-(U$6-DAT2-Pad9)") (class "Default")
      (node (ref "U$6") (pin "9") (pinfunction "DAT2_9") (pintype "bidirectional"))
    )
    (net (code "148") (name "unconnected-(U$6-WRITE_PROTECT-PadWP)") (class "Default")
      (node (ref "U$6") (pin "WP") (pinfunction "WRITE_PROTECT_WP") (pintype "passive"))
    )
    (net (code "149") (name "unconnected-(U$8-TRI-Pad1)") (class "Default")
      (node (ref "U$8") (pin "1") (pinfunction "TRI_1") (pintype "input"))
    )
  )
)
